# CAN.net
KiCad netlist of a schematic drawn in Altium Designer
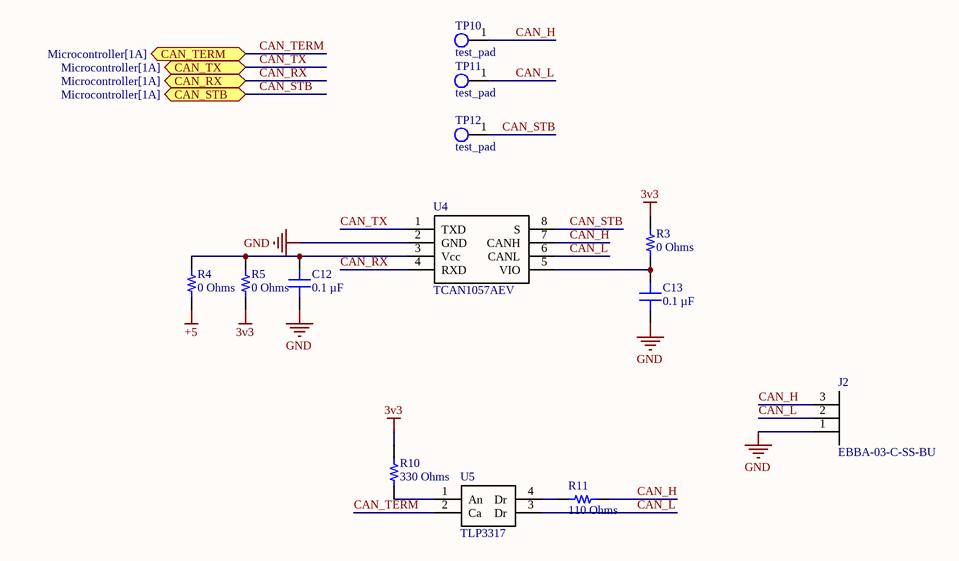
[diagram p0: CAN.SchDoc]

(export (version "E")
  (design (tool "Eeschema 10.0.6"))
  (components
    (comp (ref "C12")
      (value "0.1 µF")
      (footprint "CAP 0603_1608")
      (description "CAP CER 0.1UF 50V X7R 0603")
      (fields
        (field (name "PART NUMBER") "CL10B104KB8NNNC")
        (field (name "MANUFACTURER") "Samsung Electro-Mechanics")
      )
      (libsource (lib "Celestial Altium Library - altium_library") (part "Capacitor"))
    )
    (comp (ref "C13")
      (value "0.1 µF")
      (footprint "CAP 0603_1608")
      (description "CAP CER 0.1UF 50V X7R 0603")
      (fields
        (field (name "PART NUMBER") "CL10B104KB8NNNC")
        (field (name "MANUFACTURER") "Samsung Electro-Mechanics")
      )
      (libsource (lib "Celestial Altium Library - altium_library") (part "Capacitor"))
    )
    (comp (ref "J2")
      (value "EBBA-03-C-SS-BU")
      (footprint "EBBA-03-C-SS-BU")
      (description "Screw Terminal")
      (libsource (lib "2020-09-26_17-27-19") (part "EBBA-03-C-SS-BU"))
    )
    (comp (ref "R3")
      (value "0 Ohms")
      (footprint "RES 0603_1608")
      (description "RES 0 OHM JUMPER 1/10W 0603")
      (fields
        (field (name "PART NUMBER") "RMCF0603ZT0R00")
        (field (name "MANUFACTURER") "Stackpole Electronics Inc")
      )
      (libsource (lib "Celestial Altium Library - altium_library") (part "Resistor"))
    )
    (comp (ref "R4")
      (value "0 Ohms")
      (footprint "RES 0603_1608")
      (description "RES 0 OHM JUMPER 1/10W 0603")
      (fields
        (field (name "PART NUMBER") "RMCF0603ZT0R00")
        (field (name "MANUFACTURER") "Stackpole Electronics Inc")
      )
      (libsource (lib "Celestial Altium Library - altium_library") (part "Resistor"))
    )
    (comp (ref "R5")
      (value "0 Ohms")
      (footprint "RES 0603_1608")
      (description "RES 0 OHM JUMPER 1/10W 0603")
      (fields
        (field (name "PART NUMBER") "RMCF0603ZT0R00")
        (field (name "MANUFACTURER") "Stackpole Electronics Inc")
      )
      (libsource (lib "Celestial Altium Library - altium_library") (part "Resistor"))
    )
    (comp (ref "R10")
      (value "330 Ohms")
      (footprint "RES 0603_1608")
      (description "RES SMD 330 OHM 5% 1/10W 0603")
      (fields (field (name "PART NUMBER") "CR0603-JW-331ELF") (field (name "MANUFACTURER") "Bourns Inc."))
      (libsource (lib "Celestial Altium Library - altium_library") (part "Resistor"))
    )
    (comp (ref "R11")
      (value "110 Ohms")
      (footprint "RES 0603_1608")
      (description "RES 110 OHM 1% 1/10W 0603")
      (fields
        (field (name "PART NUMBER") "RMCF0603FT110R")
        (field (name "MANUFACTURER") "Stackpole Electronics Inc")
      )
      (libsource (lib "Celestial Altium Library - altium_library") (part "Resistor"))
    )
    (comp (ref "TP10")
      (value "test_pad")
      (footprint "2mm TP")
      (description "Test pad for ICT")
      (libsource (lib "2020-09-26_17-27-19") (part "test_pad"))
    )
    (comp (ref "TP11")
      (value "test_pad")
      (footprint "2mm TP")
      (description "Test pad for ICT")
      (libsource (lib "2020-09-26_17-27-19") (part "test_pad"))
    )
    (comp (ref "TP12")
      (value "test_pad")
      (footprint "2mm TP")
      (description "Test pad for ICT")
      (libsource (lib "2020-09-26_17-27-19") (part "test_pad"))
    )
    (comp (ref "U4")
      (value "TCAN1057AEV")
      (footprint "TCAN1057AEV")
      (libsource (lib "2020-09-26_17-27-19") (part "TCAN1057AEV"))
    )
    (comp (ref "U5")
      (value "TLP3317")
      (footprint "TLP3317")
      (libsource (lib "2020-09-26_17-27-19") (part "TLP3317"))
    )
  )
  (nets
    (net (code "1") (name "+5") (class "Default")
      (node (ref "R4") (pin "1") (pinfunction "1_1") (pintype "passive"))
    )
    (net (code "2") (name "/CAN_H") (class "Default")
      (node (ref "J2") (pin "3") (pintype "passive"))
      (node (ref "R11") (pin "1") (pinfunction "1_1") (pintype "passive"))
      (node (ref "TP10") (pin "1") (pintype "passive"))
      (node (ref "U4") (pin "7") (pinfunction "CANH_7") (pintype "passive"))
    )
    (net (code "3") (name "/CAN_L") (class "Default")
      (node (ref "J2") (pin "2") (pintype "passive"))
      (node (ref "TP11") (pin "1") (pintype "passive"))
      (node (ref "U4") (pin "6") (pinfunction "CANL_6") (pintype "passive"))
      (node (ref "U5") (pin "3") (pinfunction "Dr_3") (pintype "passive"))
    )
    (net (code "4") (name "/CAN_RX") (class "Default")
      (node (ref "U4") (pin "4") (pinfunction "RXD_4") (pintype "passive"))
    )
    (net (code "5") (name "/CAN_STB") (class "Default")
      (node (ref "TP12") (pin "1") (pintype "passive"))
      (node (ref "U4") (pin "8") (pinfunction "S_8") (pintype "passive"))
    )
    (net (code "6") (name "/CAN_TERM") (class "Default")
      (node (ref "U5") (pin "2") (pinfunction "Ca_2") (pintype "passive"))
    )
    (net (code "7") (name "/CAN_TX") (class "Default")
      (node (ref "U4") (pin "1") (pinfunction "TXD_1") (pintype "passive"))
    )
    (net (code "8") (name "3v3") (class "Default")
      (node (ref "R10") (pin "2") (pinfunction "2_2") (pintype "passive"))
      (node (ref "R3") (pin "2") (pinfunction "2_2") (pintype "passive"))
      (node (ref "R5") (pin "1") (pinfunction "1_1") (pintype "passive"))
    )
    (net (code "9") (name "GND") (class "Default")
      (node (ref "C12") (pin "1") (pinfunction "1_1") (pintype "passive"))
      (node (ref "C13") (pin "1") (pinfunction "1_1") (pintype "passive"))
      (node (ref "J2") (pin "1") (pintype "passive"))
      (node (ref "U4") (pin "2") (pinfunction "GND_2") (pintype "passive"))
    )
    (net (code "10") (name "Net-(R11-Pad2)") (class "Default")
      (node (ref "R11") (pin "2") (pinfunction "2_2") (pintype "passive"))
      (node (ref "U5") (pin "4") (pinfunction "Dr_4") (pintype "passive"))
    )
    (net (code "11") (name "Net-(U4-VIO)") (class "Default")
      (node (ref "C13") (pin "2") (pinfunction "2_2") (pintype "passive"))
      (node (ref "R3") (pin "1") (pinfunction "1_1") (pintype "passive"))
      (node (ref "U4") (pin "5") (pinfunction "VIO_5") (pintype "passive"))
    )
    (net (code "12") (name "Net-(U4-Vcc)") (class "Default")
      (node (ref "C12") (pin "2") (pinfunction "2_2") (pintype "passive"))
      (node (ref "R4") (pin "2") (pinfunction "2_2") (pintype "passive"))
      (node (ref "R5") (pin "2") (pinfunction "2_2") (pintype "passive"))
      (node (ref "U4") (pin "3") (pinfunction "Vcc_3") (pintype "passive"))
    )
    (net (code "13") (name "Net-(U5-An)") (class "Default")
      (node (ref "R10") (pin "1") (pinfunction "1_1") (pintype "passive"))
      (node (ref "U5") (pin "1") (pinfunction "An_1") (pintype "passive"))
    )
  )
)
